# ESP32-Mini1-B.net
KiCad netlist of a schematic drawn in EAGLE
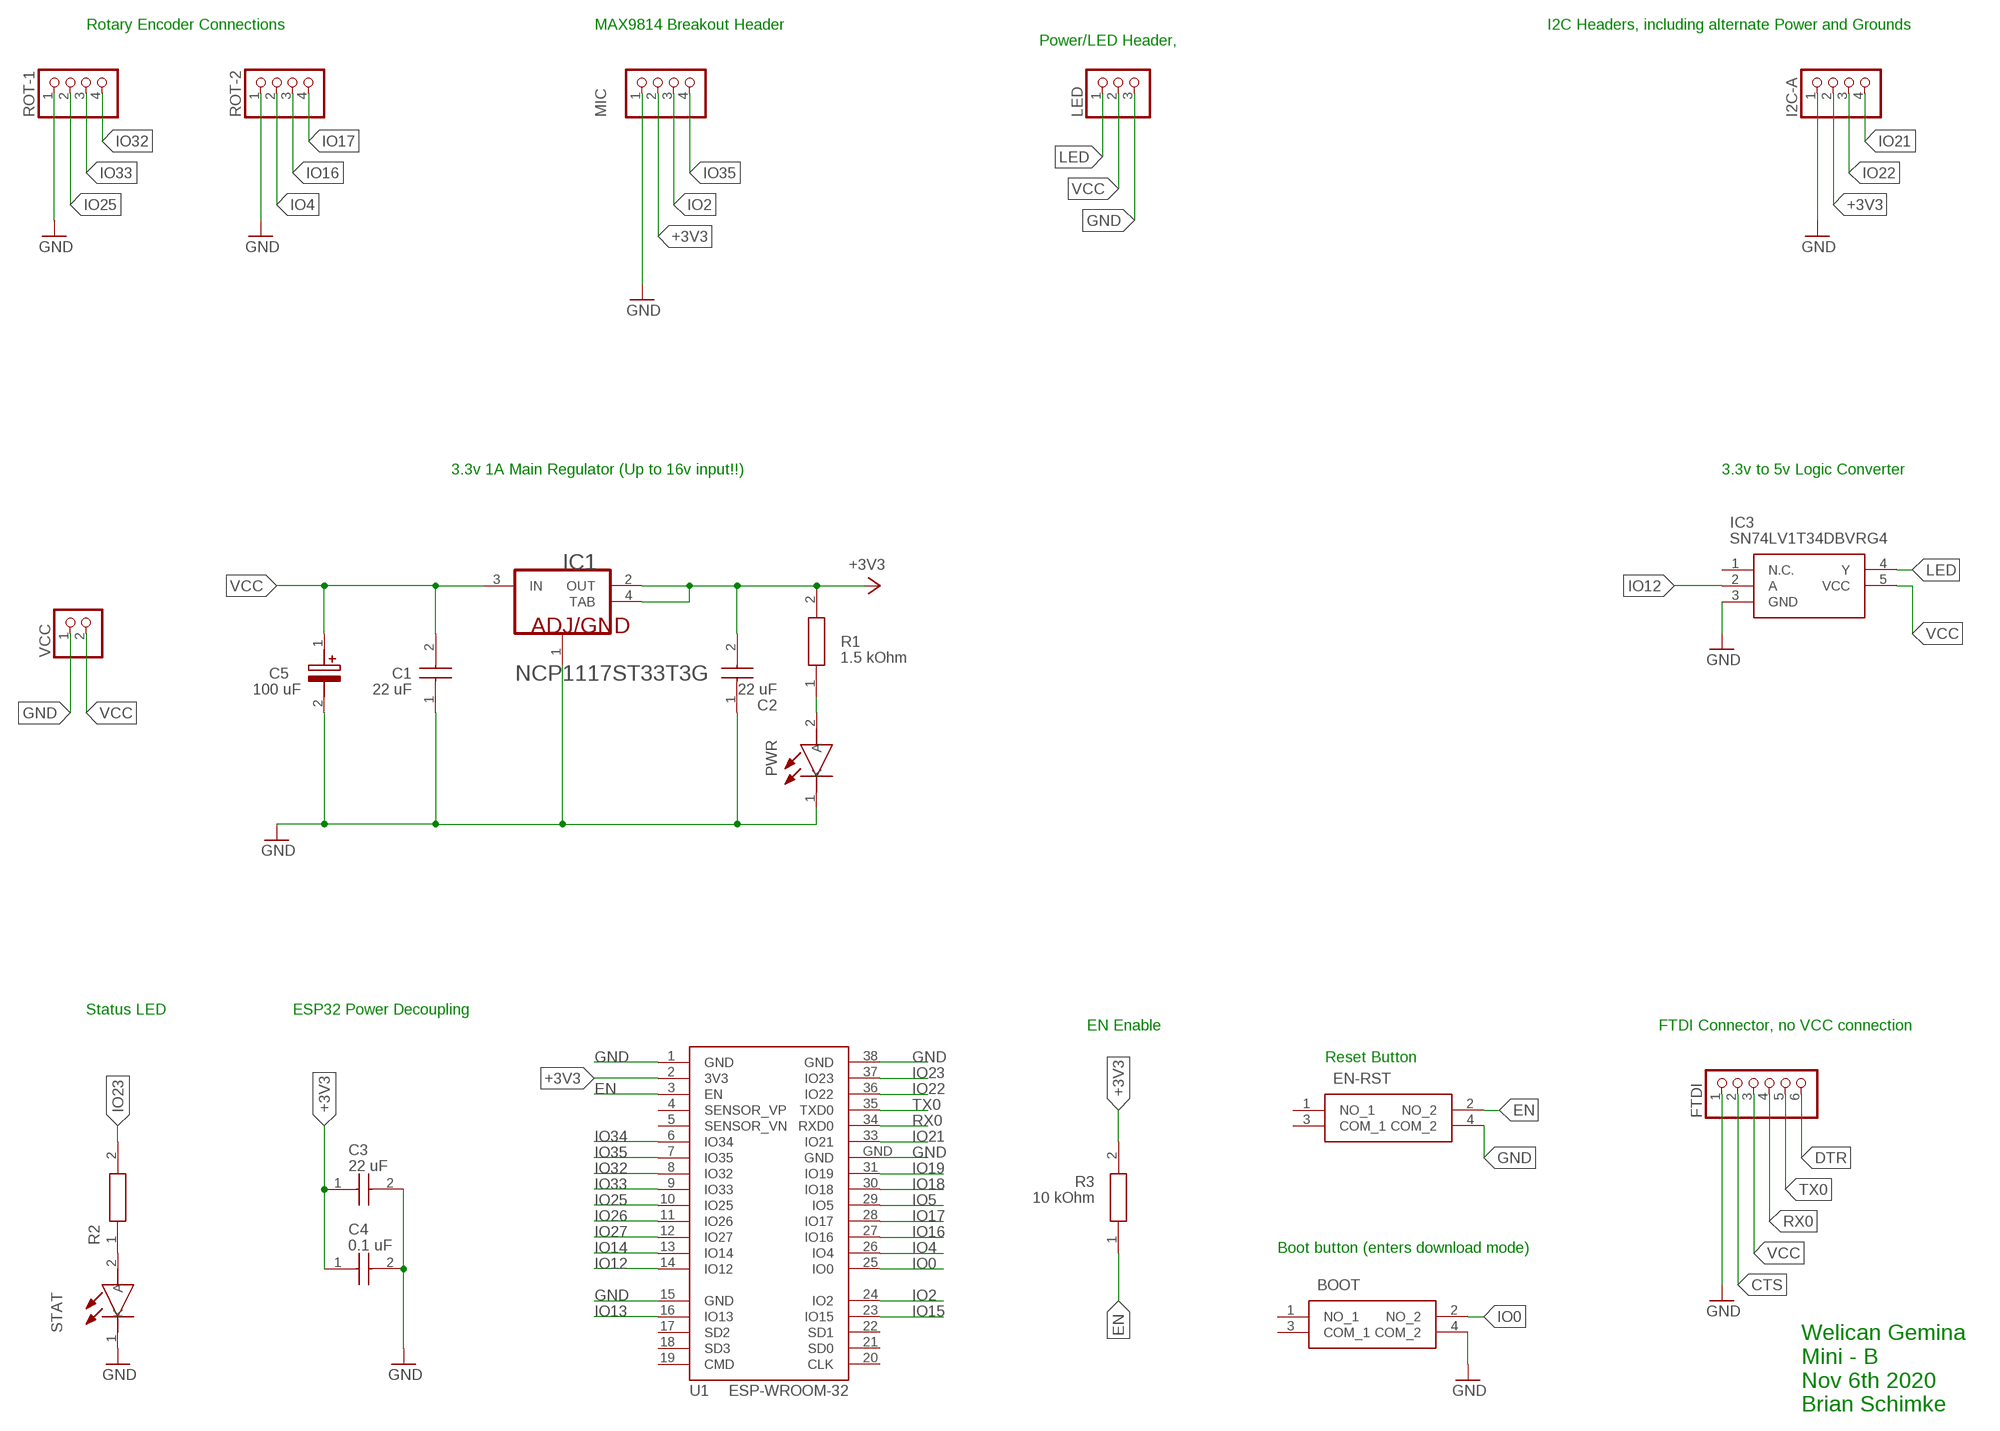
[diagram p0: schematic, sheet 1]

(export (version "E")
  (design (tool "Eeschema 10.0.6"))
  (components
    (comp (ref "BOOT")
      (value "PTS647SK70SMTR2LFS")
      (footprint "eagle-import:PTS647SK70SMTR2LFS")
      (fields (field (name "MOUSER_PART_NUMBER") "611-PTS647SK70SMTR2L"))
      (libsource (lib "eagle-import") (part "PTS647SK70SMTR2LFS"))
    )
    (comp (ref "C1")
      (value "22 uF")
      (footprint "eagle-import:CAPC3216X180N")
      (fields
        (field (name "MANUFACTURER_PART_NUMBER") "C1206C226M4PACTU")
        (field (name "MOUSER_PART_NUMBER") "80-C1206C226M4P")
      )
      (libsource (lib "eagle-import") (part "C1206C226M4PACTU"))
    )
    (comp (ref "C2")
      (value "22 uF")
      (footprint "eagle-import:CAPC3216X180N")
      (fields
        (field (name "MANUFACTURER_PART_NUMBER") "C1206C226M4PACTU")
        (field (name "MOUSER_PART_NUMBER") "80-C1206C226M4P")
      )
      (libsource (lib "eagle-import") (part "C1206C226M4PACTU"))
    )
    (comp (ref "C3")
      (value "22 uF")
      (footprint "eagle-import:CAPC3216X180N")
      (fields
        (field (name "MANUFACTURER_PART_NUMBER") "C1206C226M4PACTU")
        (field (name "MOUSER_PART_NUMBER") "80-C1206C226M4P")
      )
      (libsource (lib "eagle-import") (part "C1206C226M4PACTU"))
    )
    (comp (ref "C4")
      (value "0.1 uF")
      (footprint "eagle-import:CAPC3216X180N")
      (fields
        (field (name "MANUFACTURER_PART_NUMBER") "C1206C226M4PACTU")
        (field (name "MOUSER_PART_NUMBER") "80-C1206C226M4P")
      )
      (libsource (lib "eagle-import") (part "C1206C226M4PACTU"))
    )
    (comp (ref "C5")
      (value "100 uF")
      (footprint "eagle-import:CAPAE660X770N")
      (fields
        (field (name "MANUFACTURER_PART_NUMBER") "865080445010")
        (field (name "MOUSER_PART_NUMBER") "710-865080445010")
      )
      (libsource (lib "eagle-import") (part "865080445010"))
    )
    (comp (ref "EN-RST")
      (value "PTS647SK70SMTR2LFS")
      (footprint "eagle-import:PTS647SK70SMTR2LFS")
      (fields (field (name "MOUSER_PART_NUMBER") "611-PTS647SK70SMTR2L"))
      (libsource (lib "eagle-import") (part "PTS647SK70SMTR2LFS"))
    )
    (comp (ref "FTDI")
      (value "PINHD-1X6")
      (footprint "eagle-import:1X06")
      (libsource (lib "eagle-import") (part "PINHD-1X6"))
    )
    (comp (ref "I2C-A")
      (value "PINHD-1X4")
      (footprint "eagle-import:1X04")
      (libsource (lib "eagle-import") (part "PINHD-1X4"))
    )
    (comp (ref "IC1")
      (value "ON_SEMICONDUCTOR_NCP1117ST33T3GON_SEMICONDUCTOR_NCP1117ST33T3G_0_0")
      (footprint "eagle-import:ON_SEMICONDUCTOR_NCP1117ST33T3G_0")
      (fields
        (field (name "MF") "ON Semiconductor")
        (field (name "MPN") "NCP1117ST33T3G")
        (field (name "TOLERANCE") "1%")
      )
      (libsource (lib "eagle-import") (part "ON_SEMICONDUCTOR_NCP1117ST33T3GON_SEMICONDUCTOR_NCP1117ST33T3G_0_0"))
    )
    (comp (ref "IC3")
      (value "SN74LV1T34DBVRG4")
      (footprint "eagle-import:SOT95P280X145-5N")
      (fields (field (name "MOUSER_PART_NUMBER") "595-SN74LV1T34DBVRG4"))
      (libsource (lib "eagle-import") (part "SN74LV1T34DBVRG4"))
    )
    (comp (ref "LED")
      (value "PINHD-1X3")
      (footprint "eagle-import:1X03")
      (libsource (lib "eagle-import") (part "PINHD-1X3"))
    )
    (comp (ref "MIC")
      (value "PINHD-1X4")
      (footprint "eagle-import:1X04")
      (libsource (lib "eagle-import") (part "PINHD-1X4"))
    )
    (comp (ref "PWR")
      (value "150120AS75000")
      (footprint "eagle-import:LEDSC320X160X78-2N")
      (fields (field (name "MOUSER_PART_NUMBER") "710-150120AS75000"))
      (libsource (lib "eagle-import") (part "150120AS75000"))
    )
    (comp (ref "R1")
      (value "1.5 kOhm")
      (footprint "eagle-import:RESC3216X60N")
      (fields
        (field (name "MANUFACTURER_PART_NUMBER") "CRCW12061K00FKEB")
        (field (name "MOUSER_PART_NUMBER") "71-CRCW12061K00FKEB")
      )
      (libsource (lib "eagle-import") (part "CRCW12061K00FKEB"))
    )
    (comp (ref "R2")
      (value "CRCW12061K00FKEB")
      (footprint "eagle-import:RESC3216X60N")
      (fields (field (name "MOUSER_PART_NUMBER") "71-CRCW12061K00FKEB"))
      (libsource (lib "eagle-import") (part "CRCW12061K00FKEB"))
    )
    (comp (ref "R3")
      (value "10 kOhm")
      (footprint "eagle-import:RESC3216X60N")
      (fields
        (field (name "MANUFACTURER_PART_NUMBER") "CRCW12061K00FKEB")
        (field (name "MOUSER_PART_NUMBER") "71-CRCW12061K00FKEB")
      )
      (libsource (lib "eagle-import") (part "CRCW12061K00FKEB"))
    )
    (comp (ref "ROT-1")
      (value "PINHD-1X4")
      (footprint "eagle-import:1X04")
      (libsource (lib "eagle-import") (part "PINHD-1X4"))
    )
    (comp (ref "ROT-2")
      (value "PINHD-1X4")
      (footprint "eagle-import:1X04")
      (libsource (lib "eagle-import") (part "PINHD-1X4"))
    )
    (comp (ref "STAT")
      (value "150120AS75000")
      (footprint "eagle-import:LEDSC320X160X78-2N")
      (fields (field (name "MOUSER_PART_NUMBER") "710-150120AS75000"))
      (libsource (lib "eagle-import") (part "150120AS75000"))
    )
    (comp (ref "U1")
      (value "ESP-WROOM-32")
      (footprint "eagle-import:ESP-WROOM-32")
      (libsource (lib "eagle-import") (part "ESP-WROOM-32"))
    )
    (comp (ref "VCC")
      (value "PINHD-1X2")
      (footprint "eagle-import:1X02")
      (libsource (lib "eagle-import") (part "PINHD-1X2"))
    )
  )
  (nets
    (net (code "1") (name "+3V3") (class "Default")
      (node (ref "C2") (pin "2") (pinfunction "2_2") (pintype "bidirectional"))
      (node (ref "C3") (pin "1") (pinfunction "1_1") (pintype "bidirectional"))
      (node (ref "C4") (pin "1") (pinfunction "1_1") (pintype "bidirectional"))
      (node (ref "I2C-A") (pin "2") (pinfunction "2_2") (pintype "passive"))
      (node (ref "IC1") (pin "2") (pinfunction "OUT_2") (pintype "power_in"))
      (node (ref "IC1") (pin "4") (pinfunction "TAB_4") (pintype "passive"))
      (node (ref "MIC") (pin "2") (pinfunction "2_2") (pintype "passive"))
      (node (ref "R1") (pin "2") (pinfunction "2_2") (pintype "bidirectional"))
      (node (ref "R3") (pin "2") (pinfunction "2_2") (pintype "bidirectional"))
      (node (ref "U1") (pin "2") (pinfunction "3V3_2") (pintype "power_in"))
    )
    (net (code "2") (name "/IO5") (class "Default")
      (node (ref "U1") (pin "29") (pinfunction "IO5_29") (pintype "bidirectional"))
    )
    (net (code "3") (name "/IO13") (class "Default")
      (node (ref "U1") (pin "16") (pinfunction "IO13_16") (pintype "bidirectional"))
    )
    (net (code "4") (name "/IO14") (class "Default")
      (node (ref "U1") (pin "13") (pinfunction "IO14_13") (pintype "bidirectional"))
    )
    (net (code "5") (name "/IO15") (class "Default")
      (node (ref "U1") (pin "23") (pinfunction "IO15_23") (pintype "bidirectional"))
    )
    (net (code "6") (name "/IO18") (class "Default")
      (node (ref "U1") (pin "30") (pinfunction "IO18_30") (pintype "bidirectional"))
    )
    (net (code "7") (name "/IO19") (class "Default")
      (node (ref "U1") (pin "31") (pinfunction "IO19_31") (pintype "bidirectional"))
    )
    (net (code "8") (name "/IO26") (class "Default")
      (node (ref "U1") (pin "11") (pinfunction "IO26_11") (pintype "bidirectional"))
    )
    (net (code "9") (name "/IO27") (class "Default")
      (node (ref "U1") (pin "12") (pinfunction "IO27_12") (pintype "bidirectional"))
    )
    (net (code "10") (name "/IO34") (class "Default")
      (node (ref "U1") (pin "6") (pinfunction "IO34_6") (pintype "bidirectional"))
    )
    (net (code "11") (name "CTS") (class "Default")
      (node (ref "FTDI") (pin "2") (pinfunction "2_2") (pintype "passive"))
    )
    (net (code "12") (name "DTR") (class "Default")
      (node (ref "FTDI") (pin "6") (pinfunction "6_6") (pintype "passive"))
    )
    (net (code "13") (name "EN") (class "Default")
      (node (ref "EN-RST") (pin "2") (pinfunction "NO_2_2") (pintype "bidirectional"))
      (node (ref "R3") (pin "1") (pinfunction "1_1") (pintype "bidirectional"))
      (node (ref "U1") (pin "3") (pinfunction "EN_3") (pintype "input"))
    )
    (net (code "14") (name "GND") (class "Default")
      (node (ref "BOOT") (pin "4") (pinfunction "COM_2_4") (pintype "bidirectional"))
      (node (ref "C1") (pin "1") (pinfunction "1_1") (pintype "bidirectional"))
      (node (ref "C2") (pin "1") (pinfunction "1_1") (pintype "bidirectional"))
      (node (ref "C3") (pin "2") (pinfunction "2_2") (pintype "bidirectional"))
      (node (ref "C4") (pin "2") (pinfunction "2_2") (pintype "bidirectional"))
      (node (ref "C5") (pin "2") (pinfunction "-_2") (pintype "bidirectional"))
      (node (ref "EN-RST") (pin "4") (pinfunction "COM_2_4") (pintype "bidirectional"))
      (node (ref "FTDI") (pin "1") (pinfunction "1_1") (pintype "passive"))
      (node (ref "I2C-A") (pin "1") (pinfunction "1_1") (pintype "passive"))
      (node (ref "IC1") (pin "1") (pinfunction "ADJ/GND_1") (pintype "passive"))
      (node (ref "IC3") (pin "3") (pinfunction "GND_3") (pintype "bidirectional"))
      (node (ref "LED") (pin "3") (pinfunction "3_3") (pintype "passive"))
      (node (ref "MIC") (pin "1") (pinfunction "1_1") (pintype "passive"))
      (node (ref "PWR") (pin "1") (pinfunction "K_1") (pintype "bidirectional"))
      (node (ref "ROT-1") (pin "1") (pinfunction "1_1") (pintype "passive"))
      (node (ref "ROT-2") (pin "1") (pinfunction "1_1") (pintype "passive"))
      (node (ref "STAT") (pin "1") (pinfunction "K_1") (pintype "bidirectional"))
      (node (ref "U1") (pin "1") (pinfunction "GND_1") (pintype "power_in"))
      (node (ref "U1") (pin "15") (pinfunction "GND_15") (pintype "power_in"))
      (node (ref "U1") (pin "38") (pinfunction "GND_38") (pintype "power_in"))
      (node (ref "U1") (pin "GND") (pinfunction "GND_GND") (pintype "power_in"))
      (node (ref "VCC") (pin "1") (pinfunction "1_1") (pintype "passive"))
    )
    (net (code "15") (name "IO0") (class "Default")
      (node (ref "BOOT") (pin "2") (pinfunction "NO_2_2") (pintype "bidirectional"))
      (node (ref "U1") (pin "25") (pinfunction "IO0_25") (pintype "bidirectional"))
    )
    (net (code "16") (name "IO2") (class "Default")
      (node (ref "MIC") (pin "3") (pinfunction "3_3") (pintype "passive"))
      (node (ref "U1") (pin "24") (pinfunction "IO2_24") (pintype "bidirectional"))
    )
    (net (code "17") (name "IO4") (class "Default")
      (node (ref "ROT-2") (pin "2") (pinfunction "2_2") (pintype "passive"))
      (node (ref "U1") (pin "26") (pinfunction "IO4_26") (pintype "bidirectional"))
    )
    (net (code "18") (name "IO12") (class "Default")
      (node (ref "IC3") (pin "2") (pinfunction "A_2") (pintype "bidirectional"))
      (node (ref "U1") (pin "14") (pinfunction "IO12_14") (pintype "bidirectional"))
    )
    (net (code "19") (name "IO16") (class "Default")
      (node (ref "ROT-2") (pin "3") (pinfunction "3_3") (pintype "passive"))
      (node (ref "U1") (pin "27") (pinfunction "IO16_27") (pintype "bidirectional"))
    )
    (net (code "20") (name "IO17") (class "Default")
      (node (ref "ROT-2") (pin "4") (pinfunction "4_4") (pintype "passive"))
      (node (ref "U1") (pin "28") (pinfunction "IO17_28") (pintype "bidirectional"))
    )
    (net (code "21") (name "IO21") (class "Default")
      (node (ref "I2C-A") (pin "4") (pinfunction "4_4") (pintype "passive"))
      (node (ref "U1") (pin "33") (pinfunction "IO21_33") (pintype "bidirectional"))
    )
    (net (code "22") (name "IO22") (class "Default")
      (node (ref "I2C-A") (pin "3") (pinfunction "3_3") (pintype "passive"))
      (node (ref "U1") (pin "36") (pinfunction "IO22_36") (pintype "bidirectional"))
    )
    (net (code "23") (name "IO23") (class "Default")
      (node (ref "R2") (pin "2") (pinfunction "2_2") (pintype "bidirectional"))
      (node (ref "U1") (pin "37") (pinfunction "IO23_37") (pintype "bidirectional"))
    )
    (net (code "24") (name "IO25") (class "Default")
      (node (ref "ROT-1") (pin "2") (pinfunction "2_2") (pintype "passive"))
      (node (ref "U1") (pin "10") (pinfunction "IO25_10") (pintype "bidirectional"))
    )
    (net (code "25") (name "IO32") (class "Default")
      (node (ref "ROT-1") (pin "4") (pinfunction "4_4") (pintype "passive"))
      (node (ref "U1") (pin "8") (pinfunction "IO32_8") (pintype "bidirectional"))
    )
    (net (code "26") (name "IO33") (class "Default")
      (node (ref "ROT-1") (pin "3") (pinfunction "3_3") (pintype "passive"))
      (node (ref "U1") (pin "9") (pinfunction "IO33_9") (pintype "bidirectional"))
    )
    (net (code "27") (name "IO35") (class "Default")
      (node (ref "MIC") (pin "4") (pinfunction "4_4") (pintype "passive"))
      (node (ref "U1") (pin "7") (pinfunction "IO35_7") (pintype "bidirectional"))
    )
    (net (code "28") (name "LED") (class "Default")
      (node (ref "IC3") (pin "4") (pinfunction "Y_4") (pintype "bidirectional"))
      (node (ref "LED") (pin "1") (pinfunction "1_1") (pintype "passive"))
    )
    (net (code "29") (name "Net-(PWR-A)") (class "Default")
      (node (ref "PWR") (pin "2") (pinfunction "A_2") (pintype "bidirectional"))
      (node (ref "R1") (pin "1") (pinfunction "1_1") (pintype "bidirectional"))
    )
    (net (code "30") (name "Net-(STAT-A)") (class "Default")
      (node (ref "R2") (pin "1") (pinfunction "1_1") (pintype "bidirectional"))
      (node (ref "STAT") (pin "2") (pinfunction "A_2") (pintype "bidirectional"))
    )
    (net (code "31") (name "RX0") (class "Default")
      (node (ref "FTDI") (pin "4") (pinfunction "4_4") (pintype "passive"))
      (node (ref "U1") (pin "34") (pinfunction "RXD0_34") (pintype "bidirectional"))
    )
    (net (code "32") (name "TX0") (class "Default")
      (node (ref "FTDI") (pin "5") (pinfunction "5_5") (pintype "passive"))
      (node (ref "U1") (pin "35") (pinfunction "TXD0_35") (pintype "bidirectional"))
    )
    (net (code "33") (name "VCC") (class "Default")
      (node (ref "C1") (pin "2") (pinfunction "2_2") (pintype "bidirectional"))
      (node (ref "C5") (pin "1") (pinfunction "+_1") (pintype "bidirectional"))
      (node (ref "FTDI") (pin "3") (pinfunction "3_3") (pintype "passive"))
      (node (ref "IC1") (pin "3") (pinfunction "IN_3") (pintype "power_in"))
      (node (ref "IC3") (pin "5") (pinfunction "VCC_5") (pintype "bidirectional"))
      (node (ref "LED") (pin "2") (pinfunction "2_2") (pintype "passive"))
      (node (ref "VCC") (pin "2") (pinfunction "2_2") (pintype "passive"))
    )
    (net (code "34") (name "unconnected-(BOOT-COM_1-Pad3)") (class "Default")
      (node (ref "BOOT") (pin "3") (pinfunction "COM_1_3") (pintype "bidirectional"))
    )
    (net (code "35") (name "unconnected-(BOOT-NO_1-Pad1)") (class "Default")
      (node (ref "BOOT") (pin "1") (pinfunction "NO_1_1") (pintype "bidirectional"))
    )
    (net (code "36") (name "unconnected-(EN-RST-COM_1-Pad3)") (class "Default")
      (node (ref "EN-RST") (pin "3") (pinfunction "COM_1_3") (pintype "bidirectional"))
    )
    (net (code "37") (name "unconnected-(EN-RST-NO_1-Pad1)") (class "Default")
      (node (ref "EN-RST") (pin "1") (pinfunction "NO_1_1") (pintype "bidirectional"))
    )
    (net (code "38") (name "unconnected-(IC3-N.C.-Pad1)") (class "Default")
      (node (ref "IC3") (pin "1") (pinfunction "N.C._1") (pintype "no_connect"))
    )
    (net (code "39") (name "unconnected-(U1-CLK-Pad20)") (class "Default")
      (node (ref "U1") (pin "20") (pinfunction "CLK_20") (pintype "bidirectional"))
    )
    (net (code "40") (name "unconnected-(U1-CMD-Pad19)") (class "Default")
      (node (ref "U1") (pin "19") (pinfunction "CMD_19") (pintype "bidirectional"))
    )
    (net (code "41") (name "unconnected-(U1-SD0-Pad21)") (class "Default")
      (node (ref "U1") (pin "21") (pinfunction "SD0_21") (pintype "bidirectional"))
    )
    (net (code "42") (name "unconnected-(U1-SD1-Pad22)") (class "Default")
      (node (ref "U1") (pin "22") (pinfunction "SD1_22") (pintype "bidirectional"))
    )
    (net (code "43") (name "unconnected-(U1-SD2-Pad17)") (class "Default")
      (node (ref "U1") (pin "17") (pinfunction "SD2_17") (pintype "bidirectional"))
    )
    (net (code "44") (name "unconnected-(U1-SD3-Pad18)") (class "Default")
      (node (ref "U1") (pin "18") (pinfunction "SD3_18") (pintype "bidirectional"))
    )
    (net (code "45") (name "unconnected-(U1-SENSOR_VN-Pad5)") (class "Default")
      (node (ref "U1") (pin "5") (pinfunction "SENSOR_VN_5") (pintype "bidirectional"))
    )
    (net (code "46") (name "unconnected-(U1-SENSOR_VP-Pad4)") (class "Default")
      (node (ref "U1") (pin "4") (pinfunction "SENSOR_VP_4") (pintype "bidirectional"))
    )
  )
)
